# MC_Board.net
KiCad netlist of a schematic drawn in EAGLE
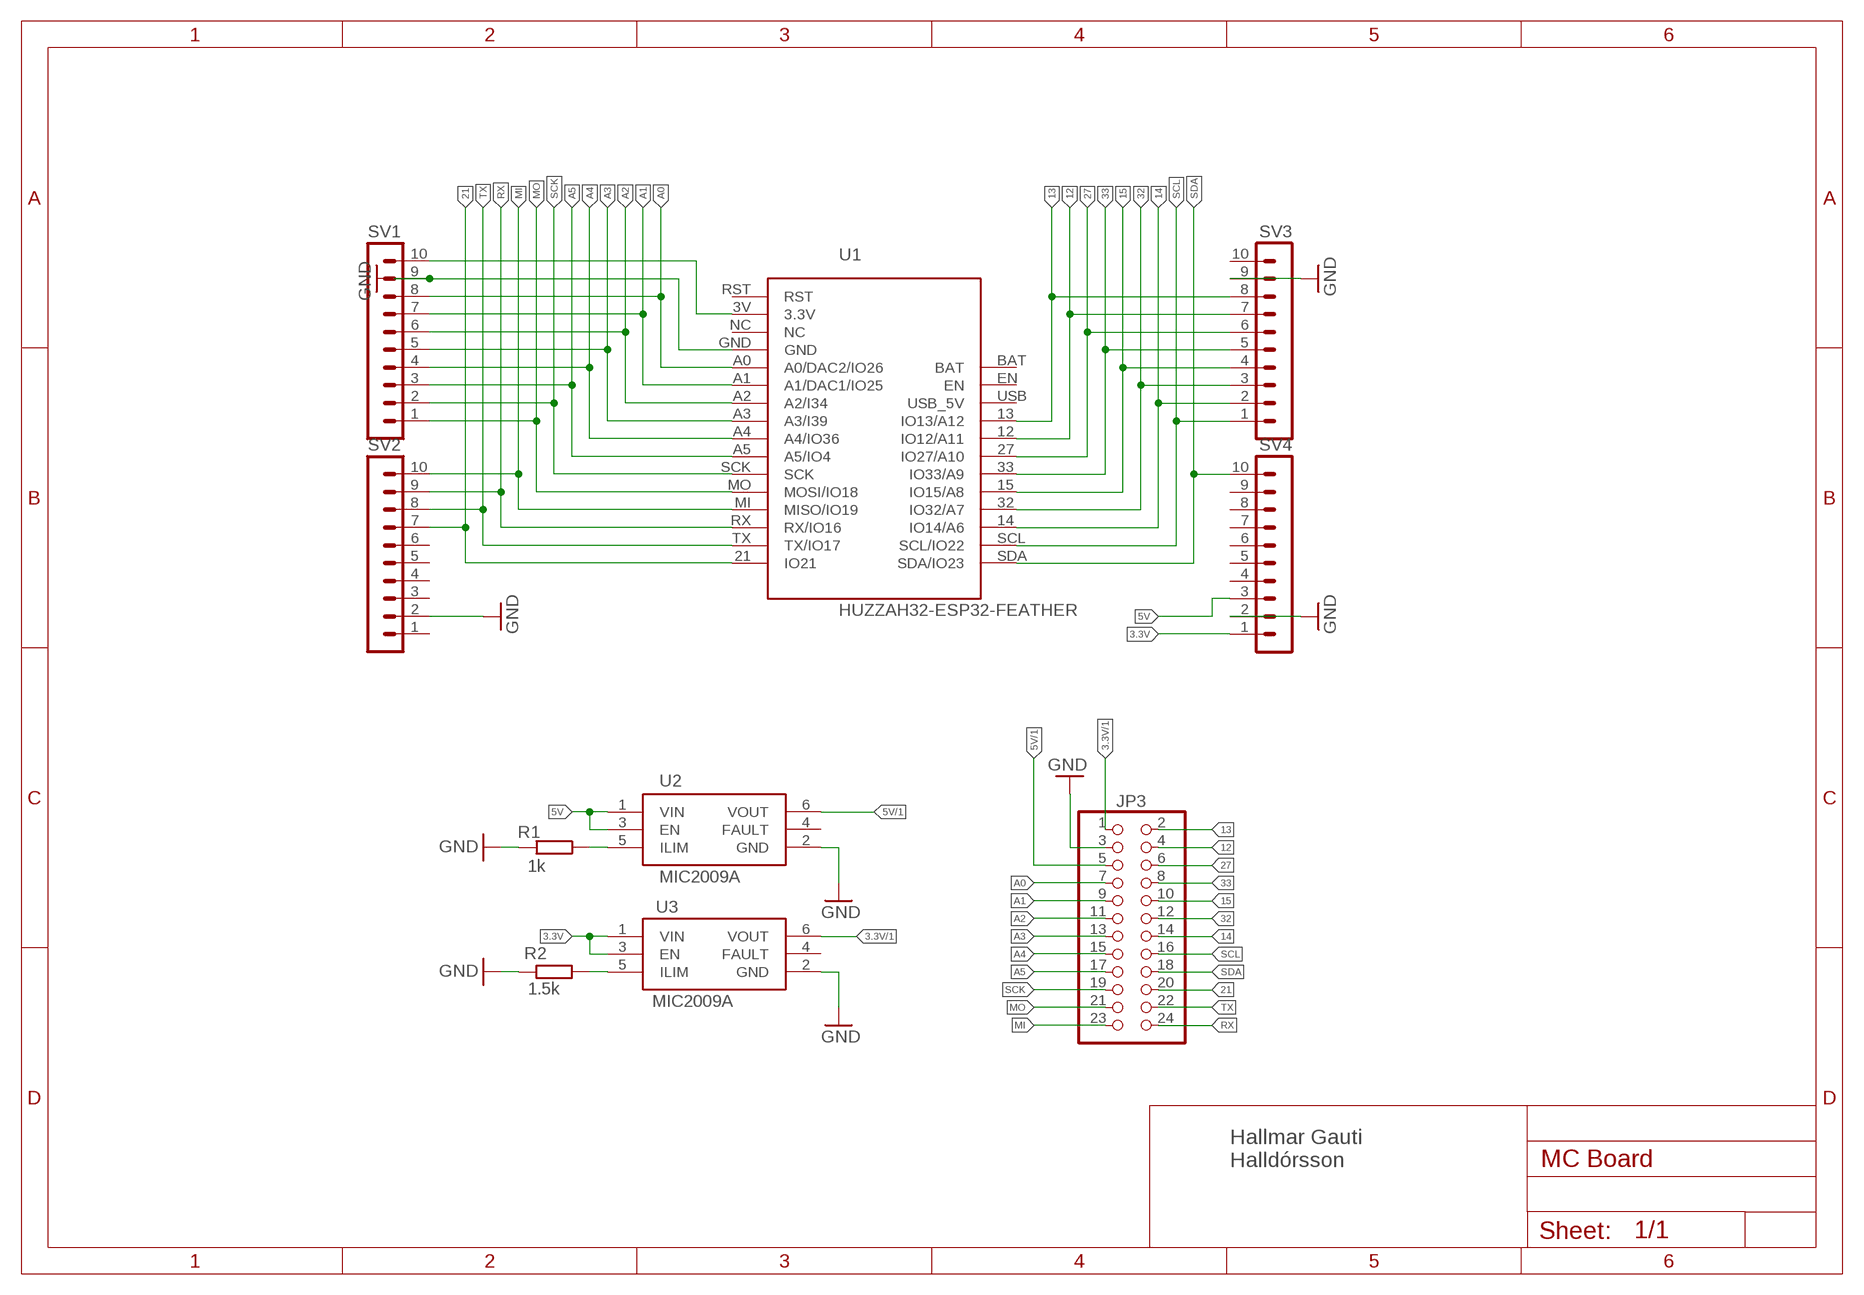
[diagram p0: schematic, sheet 1]

(export (version "E")
  (design (tool "Eeschema 10.0.6"))
  (components
    (comp (ref "JP3")
      (value "PINHD-2X12/90")
      (footprint "eagle-import:2X12_90")
      (libsource (lib "eagle-import") (part "PINHD-2X12/90"))
    )
    (comp (ref "R1")
      (value "1k")
      (footprint "eagle-import:M1206")
      (libsource (lib "eagle-import") (part "R-EU_M1206"))
    )
    (comp (ref "R2")
      (value "1.5k")
      (footprint "eagle-import:M1206")
      (libsource (lib "eagle-import") (part "R-EU_M1206"))
    )
    (comp (ref "SV1")
      (value "MA10-1")
      (footprint "eagle-import:MA10-1")
      (libsource (lib "eagle-import") (part "MA10-1"))
    )
    (comp (ref "SV2")
      (value "MA10-1")
      (footprint "eagle-import:MA10-1")
      (libsource (lib "eagle-import") (part "MA10-1"))
    )
    (comp (ref "SV3")
      (value "MA10-1")
      (footprint "eagle-import:MA10-1")
      (libsource (lib "eagle-import") (part "MA10-1"))
    )
    (comp (ref "SV4")
      (value "MA10-1")
      (footprint "eagle-import:MA10-1")
      (libsource (lib "eagle-import") (part "MA10-1"))
    )
    (comp (ref "U1")
      (value "HUZZAH32-ESP32-FEATHER")
      (footprint "eagle-import:ESP32-FEATHER")
      (libsource (lib "eagle-import") (part "HUZZAH32-ESP32-FEATHER"))
    )
    (comp (ref "U2")
      (value "MIC2009A")
      (footprint "eagle-import:MIC2009A")
      (libsource (lib "eagle-import") (part "MIC2009A"))
    )
    (comp (ref "U3")
      (value "MIC2009A")
      (footprint "eagle-import:MIC2009A")
      (libsource (lib "eagle-import") (part "MIC2009A"))
    )
  )
  (nets
    (net (code "1") (name "3.3V") (class "Default")
      (node (ref "SV4") (pin "1") (pinfunction "1_1") (pintype "passive"))
      (node (ref "U3") (pin "1") (pinfunction "VIN_1") (pintype "bidirectional"))
      (node (ref "U3") (pin "3") (pinfunction "EN_3") (pintype "bidirectional"))
    )
    (net (code "2") (name "3.3V{slash}1") (class "Default")
      (node (ref "JP3") (pin "1") (pinfunction "1_1") (pintype "passive"))
      (node (ref "U3") (pin "6") (pinfunction "VOUT_6") (pintype "bidirectional"))
    )
    (net (code "3") (name "5V") (class "Default")
      (node (ref "SV4") (pin "3") (pinfunction "3_3") (pintype "passive"))
      (node (ref "U2") (pin "1") (pinfunction "VIN_1") (pintype "bidirectional"))
      (node (ref "U2") (pin "3") (pinfunction "EN_3") (pintype "bidirectional"))
    )
    (net (code "4") (name "5V{slash}1") (class "Default")
      (node (ref "JP3") (pin "5") (pinfunction "5_5") (pintype "passive"))
      (node (ref "U2") (pin "6") (pinfunction "VOUT_6") (pintype "bidirectional"))
    )
    (net (code "5") (name "12") (class "Default")
      (node (ref "JP3") (pin "4") (pinfunction "4_4") (pintype "passive"))
      (node (ref "SV3") (pin "7") (pinfunction "7_7") (pintype "passive"))
      (node (ref "U1") (pin "12") (pinfunction "IO12/A11_12") (pintype "bidirectional"))
    )
    (net (code "6") (name "13") (class "Default")
      (node (ref "JP3") (pin "2") (pinfunction "2_2") (pintype "passive"))
      (node (ref "SV3") (pin "8") (pinfunction "8_8") (pintype "passive"))
      (node (ref "U1") (pin "13") (pinfunction "IO13/A12_13") (pintype "bidirectional"))
    )
    (net (code "7") (name "14") (class "Default")
      (node (ref "JP3") (pin "14") (pinfunction "14_14") (pintype "passive"))
      (node (ref "SV3") (pin "2") (pinfunction "2_2") (pintype "passive"))
      (node (ref "U1") (pin "14") (pinfunction "IO14/A6_14") (pintype "bidirectional"))
    )
    (net (code "8") (name "15") (class "Default")
      (node (ref "JP3") (pin "10") (pinfunction "10_10") (pintype "passive"))
      (node (ref "SV3") (pin "4") (pinfunction "4_4") (pintype "passive"))
      (node (ref "U1") (pin "15") (pinfunction "IO15/A8_15") (pintype "bidirectional"))
    )
    (net (code "9") (name "21") (class "Default")
      (node (ref "JP3") (pin "20") (pinfunction "20_20") (pintype "passive"))
      (node (ref "SV2") (pin "7") (pinfunction "7_7") (pintype "passive"))
      (node (ref "U1") (pin "21") (pinfunction "IO21_21") (pintype "bidirectional"))
    )
    (net (code "10") (name "27") (class "Default")
      (node (ref "JP3") (pin "6") (pinfunction "6_6") (pintype "passive"))
      (node (ref "SV3") (pin "6") (pinfunction "6_6") (pintype "passive"))
      (node (ref "U1") (pin "27") (pinfunction "IO27/A10_27") (pintype "bidirectional"))
    )
    (net (code "11") (name "32") (class "Default")
      (node (ref "JP3") (pin "12") (pinfunction "12_12") (pintype "passive"))
      (node (ref "SV3") (pin "3") (pinfunction "3_3") (pintype "passive"))
      (node (ref "U1") (pin "32") (pinfunction "IO32/A7_32") (pintype "bidirectional"))
    )
    (net (code "12") (name "33") (class "Default")
      (node (ref "JP3") (pin "8") (pinfunction "8_8") (pintype "passive"))
      (node (ref "SV3") (pin "5") (pinfunction "5_5") (pintype "passive"))
      (node (ref "U1") (pin "33") (pinfunction "IO33/A9_33") (pintype "bidirectional"))
    )
    (net (code "13") (name "A0") (class "Default")
      (node (ref "JP3") (pin "7") (pinfunction "7_7") (pintype "passive"))
      (node (ref "SV1") (pin "8") (pinfunction "8_8") (pintype "passive"))
      (node (ref "U1") (pin "A0") (pinfunction "A0/DAC2/IO26_A0") (pintype "bidirectional"))
    )
    (net (code "14") (name "A1") (class "Default")
      (node (ref "JP3") (pin "9") (pinfunction "9_9") (pintype "passive"))
      (node (ref "SV1") (pin "7") (pinfunction "7_7") (pintype "passive"))
      (node (ref "U1") (pin "A1") (pinfunction "A1/DAC1/IO25_A1") (pintype "bidirectional"))
    )
    (net (code "15") (name "A2") (class "Default")
      (node (ref "JP3") (pin "11") (pinfunction "11_11") (pintype "passive"))
      (node (ref "SV1") (pin "6") (pinfunction "6_6") (pintype "passive"))
      (node (ref "U1") (pin "A2") (pinfunction "A2/I34_A2") (pintype "bidirectional"))
    )
    (net (code "16") (name "A3") (class "Default")
      (node (ref "JP3") (pin "13") (pinfunction "13_13") (pintype "passive"))
      (node (ref "SV1") (pin "5") (pinfunction "5_5") (pintype "passive"))
      (node (ref "U1") (pin "A3") (pinfunction "A3/I39_A3") (pintype "bidirectional"))
    )
    (net (code "17") (name "A4") (class "Default")
      (node (ref "JP3") (pin "15") (pinfunction "15_15") (pintype "passive"))
      (node (ref "SV1") (pin "4") (pinfunction "4_4") (pintype "passive"))
      (node (ref "U1") (pin "A4") (pinfunction "A4/IO36_A4") (pintype "bidirectional"))
    )
    (net (code "18") (name "A5") (class "Default")
      (node (ref "JP3") (pin "17") (pinfunction "17_17") (pintype "passive"))
      (node (ref "SV1") (pin "3") (pinfunction "3_3") (pintype "passive"))
      (node (ref "U1") (pin "A5") (pinfunction "A5/IO4_A5") (pintype "bidirectional"))
    )
    (net (code "19") (name "GND") (class "Default")
      (node (ref "JP3") (pin "3") (pinfunction "3_3") (pintype "passive"))
      (node (ref "R1") (pin "2") (pinfunction "2_2") (pintype "passive"))
      (node (ref "R2") (pin "1") (pinfunction "1_1") (pintype "passive"))
      (node (ref "SV1") (pin "9") (pinfunction "9_9") (pintype "passive"))
      (node (ref "SV2") (pin "2") (pinfunction "2_2") (pintype "passive"))
      (node (ref "SV3") (pin "9") (pinfunction "9_9") (pintype "passive"))
      (node (ref "SV4") (pin "2") (pinfunction "2_2") (pintype "passive"))
      (node (ref "U1") (pin "GND") (pinfunction "GND_GND") (pintype "bidirectional"))
      (node (ref "U2") (pin "2") (pinfunction "GND_2") (pintype "bidirectional"))
      (node (ref "U3") (pin "2") (pinfunction "GND_2") (pintype "bidirectional"))
    )
    (net (code "20") (name "MI") (class "Default")
      (node (ref "JP3") (pin "23") (pinfunction "23_23") (pintype "passive"))
      (node (ref "SV2") (pin "10") (pinfunction "10_10") (pintype "passive"))
      (node (ref "U1") (pin "MI") (pinfunction "MISO/IO19_MI") (pintype "bidirectional"))
    )
    (net (code "21") (name "MO") (class "Default")
      (node (ref "JP3") (pin "21") (pinfunction "21_21") (pintype "passive"))
      (node (ref "SV1") (pin "1") (pinfunction "1_1") (pintype "passive"))
      (node (ref "U1") (pin "MO") (pinfunction "MOSI/IO18_MO") (pintype "bidirectional"))
    )
    (net (code "22") (name "Net-(U1-3.3V)") (class "Default")
      (node (ref "SV1") (pin "10") (pinfunction "10_10") (pintype "passive"))
      (node (ref "U1") (pin "3V") (pinfunction "3.3V_3V") (pintype "bidirectional"))
    )
    (net (code "23") (name "Net-(U2-ILIM)") (class "Default")
      (node (ref "R1") (pin "1") (pinfunction "1_1") (pintype "passive"))
      (node (ref "U2") (pin "5") (pinfunction "ILIM_5") (pintype "bidirectional"))
    )
    (net (code "24") (name "Net-(U3-ILIM)") (class "Default")
      (node (ref "R2") (pin "2") (pinfunction "2_2") (pintype "passive"))
      (node (ref "U3") (pin "5") (pinfunction "ILIM_5") (pintype "bidirectional"))
    )
    (net (code "25") (name "RX") (class "Default")
      (node (ref "JP3") (pin "24") (pinfunction "24_24") (pintype "passive"))
      (node (ref "SV2") (pin "9") (pinfunction "9_9") (pintype "passive"))
      (node (ref "U1") (pin "RX") (pinfunction "RX/IO16_RX") (pintype "bidirectional"))
    )
    (net (code "26") (name "SCK") (class "Default")
      (node (ref "JP3") (pin "19") (pinfunction "19_19") (pintype "passive"))
      (node (ref "SV1") (pin "2") (pinfunction "2_2") (pintype "passive"))
      (node (ref "U1") (pin "SCK") (pinfunction "SCK_SCK") (pintype "bidirectional"))
    )
    (net (code "27") (name "SCL") (class "Default")
      (node (ref "JP3") (pin "16") (pinfunction "16_16") (pintype "passive"))
      (node (ref "SV3") (pin "1") (pinfunction "1_1") (pintype "passive"))
      (node (ref "U1") (pin "SCL") (pinfunction "SCL/IO22_SCL") (pintype "bidirectional"))
    )
    (net (code "28") (name "SDA") (class "Default")
      (node (ref "JP3") (pin "18") (pinfunction "18_18") (pintype "passive"))
      (node (ref "SV4") (pin "10") (pinfunction "10_10") (pintype "passive"))
      (node (ref "U1") (pin "SDA") (pinfunction "SDA/IO23_SDA") (pintype "bidirectional"))
    )
    (net (code "29") (name "TX") (class "Default")
      (node (ref "JP3") (pin "22") (pinfunction "22_22") (pintype "passive"))
      (node (ref "SV2") (pin "8") (pinfunction "8_8") (pintype "passive"))
      (node (ref "U1") (pin "TX") (pinfunction "TX/IO17_TX") (pintype "bidirectional"))
    )
    (net (code "30") (name "unconnected-(SV2-Pad1)") (class "Default")
      (node (ref "SV2") (pin "1") (pinfunction "1_1") (pintype "passive"))
    )
    (net (code "31") (name "unconnected-(SV2-Pad3)") (class "Default")
      (node (ref "SV2") (pin "3") (pinfunction "3_3") (pintype "passive"))
    )
    (net (code "32") (name "unconnected-(SV2-Pad4)") (class "Default")
      (node (ref "SV2") (pin "4") (pinfunction "4_4") (pintype "passive"))
    )
    (net (code "33") (name "unconnected-(SV2-Pad5)") (class "Default")
      (node (ref "SV2") (pin "5") (pinfunction "5_5") (pintype "passive"))
    )
    (net (code "34") (name "unconnected-(SV2-Pad6)") (class "Default")
      (node (ref "SV2") (pin "6") (pinfunction "6_6") (pintype "passive"))
    )
    (net (code "35") (name "unconnected-(SV3-Pad10)") (class "Default")
      (node (ref "SV3") (pin "10") (pinfunction "10_10") (pintype "passive"))
    )
    (net (code "36") (name "unconnected-(SV4-Pad4)") (class "Default")
      (node (ref "SV4") (pin "4") (pinfunction "4_4") (pintype "passive"))
    )
    (net (code "37") (name "unconnected-(SV4-Pad5)") (class "Default")
      (node (ref "SV4") (pin "5") (pinfunction "5_5") (pintype "passive"))
    )
    (net (code "38") (name "unconnected-(SV4-Pad6)") (class "Default")
      (node (ref "SV4") (pin "6") (pinfunction "6_6") (pintype "passive"))
    )
    (net (code "39") (name "unconnected-(SV4-Pad7)") (class "Default")
      (node (ref "SV4") (pin "7") (pinfunction "7_7") (pintype "passive"))
    )
    (net (code "40") (name "unconnected-(SV4-Pad8)") (class "Default")
      (node (ref "SV4") (pin "8") (pinfunction "8_8") (pintype "passive"))
    )
    (net (code "41") (name "unconnected-(SV4-Pad9)") (class "Default")
      (node (ref "SV4") (pin "9") (pinfunction "9_9") (pintype "passive"))
    )
    (net (code "42") (name "unconnected-(U1-PadBAT)") (class "Default")
      (node (ref "U1") (pin "BAT") (pinfunction "BAT_BAT") (pintype "bidirectional"))
    )
    (net (code "43") (name "unconnected-(U1-PadEN)") (class "Default")
      (node (ref "U1") (pin "EN") (pinfunction "EN_EN") (pintype "bidirectional"))
    )
    (net (code "44") (name "unconnected-(U1-PadNC)") (class "Default")
      (node (ref "U1") (pin "NC") (pinfunction "NC_NC") (pintype "bidirectional"))
    )
    (net (code "45") (name "unconnected-(U1-PadRST)") (class "Default")
      (node (ref "U1") (pin "RST") (pinfunction "RST_RST") (pintype "bidirectional"))
    )
    (net (code "46") (name "unconnected-(U1-USB_5V-PadUSB)") (class "Default")
      (node (ref "U1") (pin "USB") (pinfunction "USB_5V_USB") (pintype "bidirectional"))
    )
    (net (code "47") (name "unconnected-(U2-FAULT-Pad4)") (class "Default")
      (node (ref "U2") (pin "4") (pinfunction "FAULT_4") (pintype "bidirectional"))
    )
    (net (code "48") (name "unconnected-(U3-FAULT-Pad4)") (class "Default")
      (node (ref "U3") (pin "4") (pinfunction "FAULT_4") (pintype "bidirectional"))
    )
  )
)
